# Digital_Port_K_Default_State_DIP.net
KiCad netlist of a schematic drawn in Altium Designer
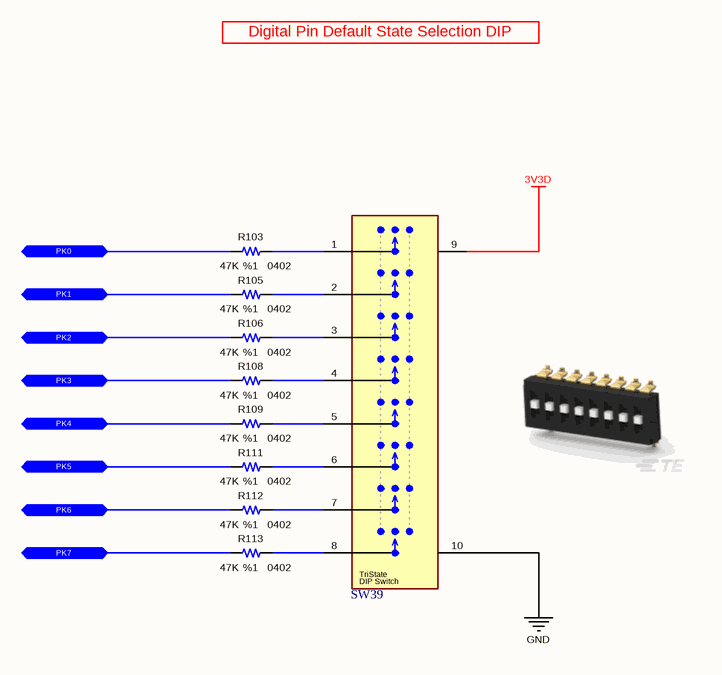
[diagram p0: Digital Port K Default State DIP.SchDoc]

(export (version "E")
  (design (tool "Eeschema 10.0.6"))
  (components
    (comp (ref "R103")
      (value "47K")
      (footprint "RESISTOR_0402")
      (description "Thick Film Resistors - SMD 1/16 W 47 Kohms 1%")
      (fields
        (field (name "MANUFACTURER PART NUMBER") "CRCW040247K0FKED")
        (field (name "MOUSER PART NUMBER") "71-CRCW0402-47K-E3")
        (field (name "TOLERANCE") "%1")
        (field (name "CASE") "0402")
      )
      (libsource (lib "Ovoo_Library") (part "Resistor - 47K"))
    )
    (comp (ref "R105")
      (value "47K")
      (footprint "RESISTOR_0402")
      (description "Thick Film Resistors - SMD 1/16 W 47 Kohms 1%")
      (fields
        (field (name "MANUFACTURER PART NUMBER") "CRCW040247K0FKED")
        (field (name "MOUSER PART NUMBER") "71-CRCW0402-47K-E3")
        (field (name "TOLERANCE") "%1")
        (field (name "CASE") "0402")
      )
      (libsource (lib "Ovoo_Library") (part "Resistor - 47K"))
    )
    (comp (ref "R106")
      (value "47K")
      (footprint "RESISTOR_0402")
      (description "Thick Film Resistors - SMD 1/16 W 47 Kohms 1%")
      (fields
        (field (name "MANUFACTURER PART NUMBER") "CRCW040247K0FKED")
        (field (name "MOUSER PART NUMBER") "71-CRCW0402-47K-E3")
        (field (name "TOLERANCE") "%1")
        (field (name "CASE") "0402")
      )
      (libsource (lib "Ovoo_Library") (part "Resistor - 47K"))
    )
    (comp (ref "R108")
      (value "47K")
      (footprint "RESISTOR_0402")
      (description "Thick Film Resistors - SMD 1/16 W 47 Kohms 1%")
      (fields
        (field (name "MANUFACTURER PART NUMBER") "CRCW040247K0FKED")
        (field (name "MOUSER PART NUMBER") "71-CRCW0402-47K-E3")
        (field (name "TOLERANCE") "%1")
        (field (name "CASE") "0402")
      )
      (libsource (lib "Ovoo_Library") (part "Resistor - 47K"))
    )
    (comp (ref "R109")
      (value "47K")
      (footprint "RESISTOR_0402")
      (description "Thick Film Resistors - SMD 1/16 W 47 Kohms 1%")
      (fields
        (field (name "MANUFACTURER PART NUMBER") "CRCW040247K0FKED")
        (field (name "MOUSER PART NUMBER") "71-CRCW0402-47K-E3")
        (field (name "TOLERANCE") "%1")
        (field (name "CASE") "0402")
      )
      (libsource (lib "Ovoo_Library") (part "Resistor - 47K"))
    )
    (comp (ref "R111")
      (value "47K")
      (footprint "RESISTOR_0402")
      (description "Thick Film Resistors - SMD 1/16 W 47 Kohms 1%")
      (fields
        (field (name "MANUFACTURER PART NUMBER") "CRCW040247K0FKED")
        (field (name "MOUSER PART NUMBER") "71-CRCW0402-47K-E3")
        (field (name "TOLERANCE") "%1")
        (field (name "CASE") "0402")
      )
      (libsource (lib "Ovoo_Library") (part "Resistor - 47K"))
    )
    (comp (ref "R112")
      (value "47K")
      (footprint "RESISTOR_0402")
      (description "Thick Film Resistors - SMD 1/16 W 47 Kohms 1%")
      (fields
        (field (name "MANUFACTURER PART NUMBER") "CRCW040247K0FKED")
        (field (name "MOUSER PART NUMBER") "71-CRCW0402-47K-E3")
        (field (name "TOLERANCE") "%1")
        (field (name "CASE") "0402")
      )
      (libsource (lib "Ovoo_Library") (part "Resistor - 47K"))
    )
    (comp (ref "R113")
      (value "47K")
      (footprint "RESISTOR_0402")
      (description "Thick Film Resistors - SMD 1/16 W 47 Kohms 1%")
      (fields
        (field (name "MANUFACTURER PART NUMBER") "CRCW040247K0FKED")
        (field (name "MOUSER PART NUMBER") "71-CRCW0402-47K-E3")
        (field (name "TOLERANCE") "%1")
        (field (name "CASE") "0402")
      )
      (libsource (lib "Ovoo_Library") (part "Resistor - 47K"))
    )
    (comp (ref "SW39")
      (value "DIP Switches/SIP Switches")
      (footprint "TDS08SGNNTR04")
      (description "DIP Switches/SIP Switches TRI-STATE DIP 8P G RAISED T&R")
      (fields
        (field (name "MANUFACTURER PART NUMBER") "TDS08SGNNTR04")
        (field (name "MOUSER PART NUMBER") "506-TDS08SGNNTR04")
      )
      (libsource (lib "Ovoo_Library") (part "Switch - DIP Switch (8 Pole TriState)"))
    )
  )
  (nets
    (net (code "1") (name "/PK0") (class "Default")
      (node (ref "R103") (pin "2") (pinfunction "2_2") (pintype "passive"))
    )
    (net (code "2") (name "/PK1") (class "Default")
      (node (ref "R105") (pin "2") (pinfunction "2_2") (pintype "passive"))
    )
    (net (code "3") (name "/PK2") (class "Default")
      (node (ref "R106") (pin "2") (pinfunction "2_2") (pintype "passive"))
    )
    (net (code "4") (name "/PK3") (class "Default")
      (node (ref "R108") (pin "2") (pinfunction "2_2") (pintype "passive"))
    )
    (net (code "5") (name "/PK4") (class "Default")
      (node (ref "R109") (pin "2") (pinfunction "2_2") (pintype "passive"))
    )
    (net (code "6") (name "/PK5") (class "Default")
      (node (ref "R111") (pin "2") (pinfunction "2_2") (pintype "passive"))
    )
    (net (code "7") (name "/PK6") (class "Default")
      (node (ref "R112") (pin "2") (pinfunction "2_2") (pintype "passive"))
    )
    (net (code "8") (name "/PK7") (class "Default")
      (node (ref "R113") (pin "2") (pinfunction "2_2") (pintype "passive"))
    )
    (net (code "9") (name "3V3D") (class "Default")
      (node (ref "SW39") (pin "9") (pinfunction "VCC_9") (pintype "passive"))
    )
    (net (code "10") (name "GND") (class "Default")
      (node (ref "SW39") (pin "10") (pinfunction "GND_10") (pintype "passive"))
    )
    (net (code "11") (name "Net-(R103-Pad1)") (class "Default")
      (node (ref "R103") (pin "1") (pinfunction "1_1") (pintype "passive"))
      (node (ref "SW39") (pin "1") (pinfunction "1_1") (pintype "passive"))
    )
    (net (code "12") (name "Net-(R105-Pad1)") (class "Default")
      (node (ref "R105") (pin "1") (pinfunction "1_1") (pintype "passive"))
      (node (ref "SW39") (pin "2") (pinfunction "2_2") (pintype "passive"))
    )
    (net (code "13") (name "Net-(R106-Pad1)") (class "Default")
      (node (ref "R106") (pin "1") (pinfunction "1_1") (pintype "passive"))
      (node (ref "SW39") (pin "3") (pinfunction "3_3") (pintype "passive"))
    )
    (net (code "14") (name "Net-(R108-Pad1)") (class "Default")
      (node (ref "R108") (pin "1") (pinfunction "1_1") (pintype "passive"))
      (node (ref "SW39") (pin "4") (pinfunction "4_4") (pintype "passive"))
    )
    (net (code "15") (name "Net-(R109-Pad1)") (class "Default")
      (node (ref "R109") (pin "1") (pinfunction "1_1") (pintype "passive"))
      (node (ref "SW39") (pin "5") (pinfunction "5_5") (pintype "passive"))
    )
    (net (code "16") (name "Net-(R111-Pad1)") (class "Default")
      (node (ref "R111") (pin "1") (pinfunction "1_1") (pintype "passive"))
      (node (ref "SW39") (pin "6") (pinfunction "6_6") (pintype "passive"))
    )
    (net (code "17") (name "Net-(R112-Pad1)") (class "Default")
      (node (ref "R112") (pin "1") (pinfunction "1_1") (pintype "passive"))
      (node (ref "SW39") (pin "7") (pinfunction "7_7") (pintype "passive"))
    )
    (net (code "18") (name "Net-(R113-Pad1)") (class "Default")
      (node (ref "R113") (pin "1") (pinfunction "1_1") (pintype "passive"))
      (node (ref "SW39") (pin "8") (pinfunction "8_8") (pintype "passive"))
    )
  )
)
